# pickup3.net
KiCad netlist of a schematic drawn in EasyEDA
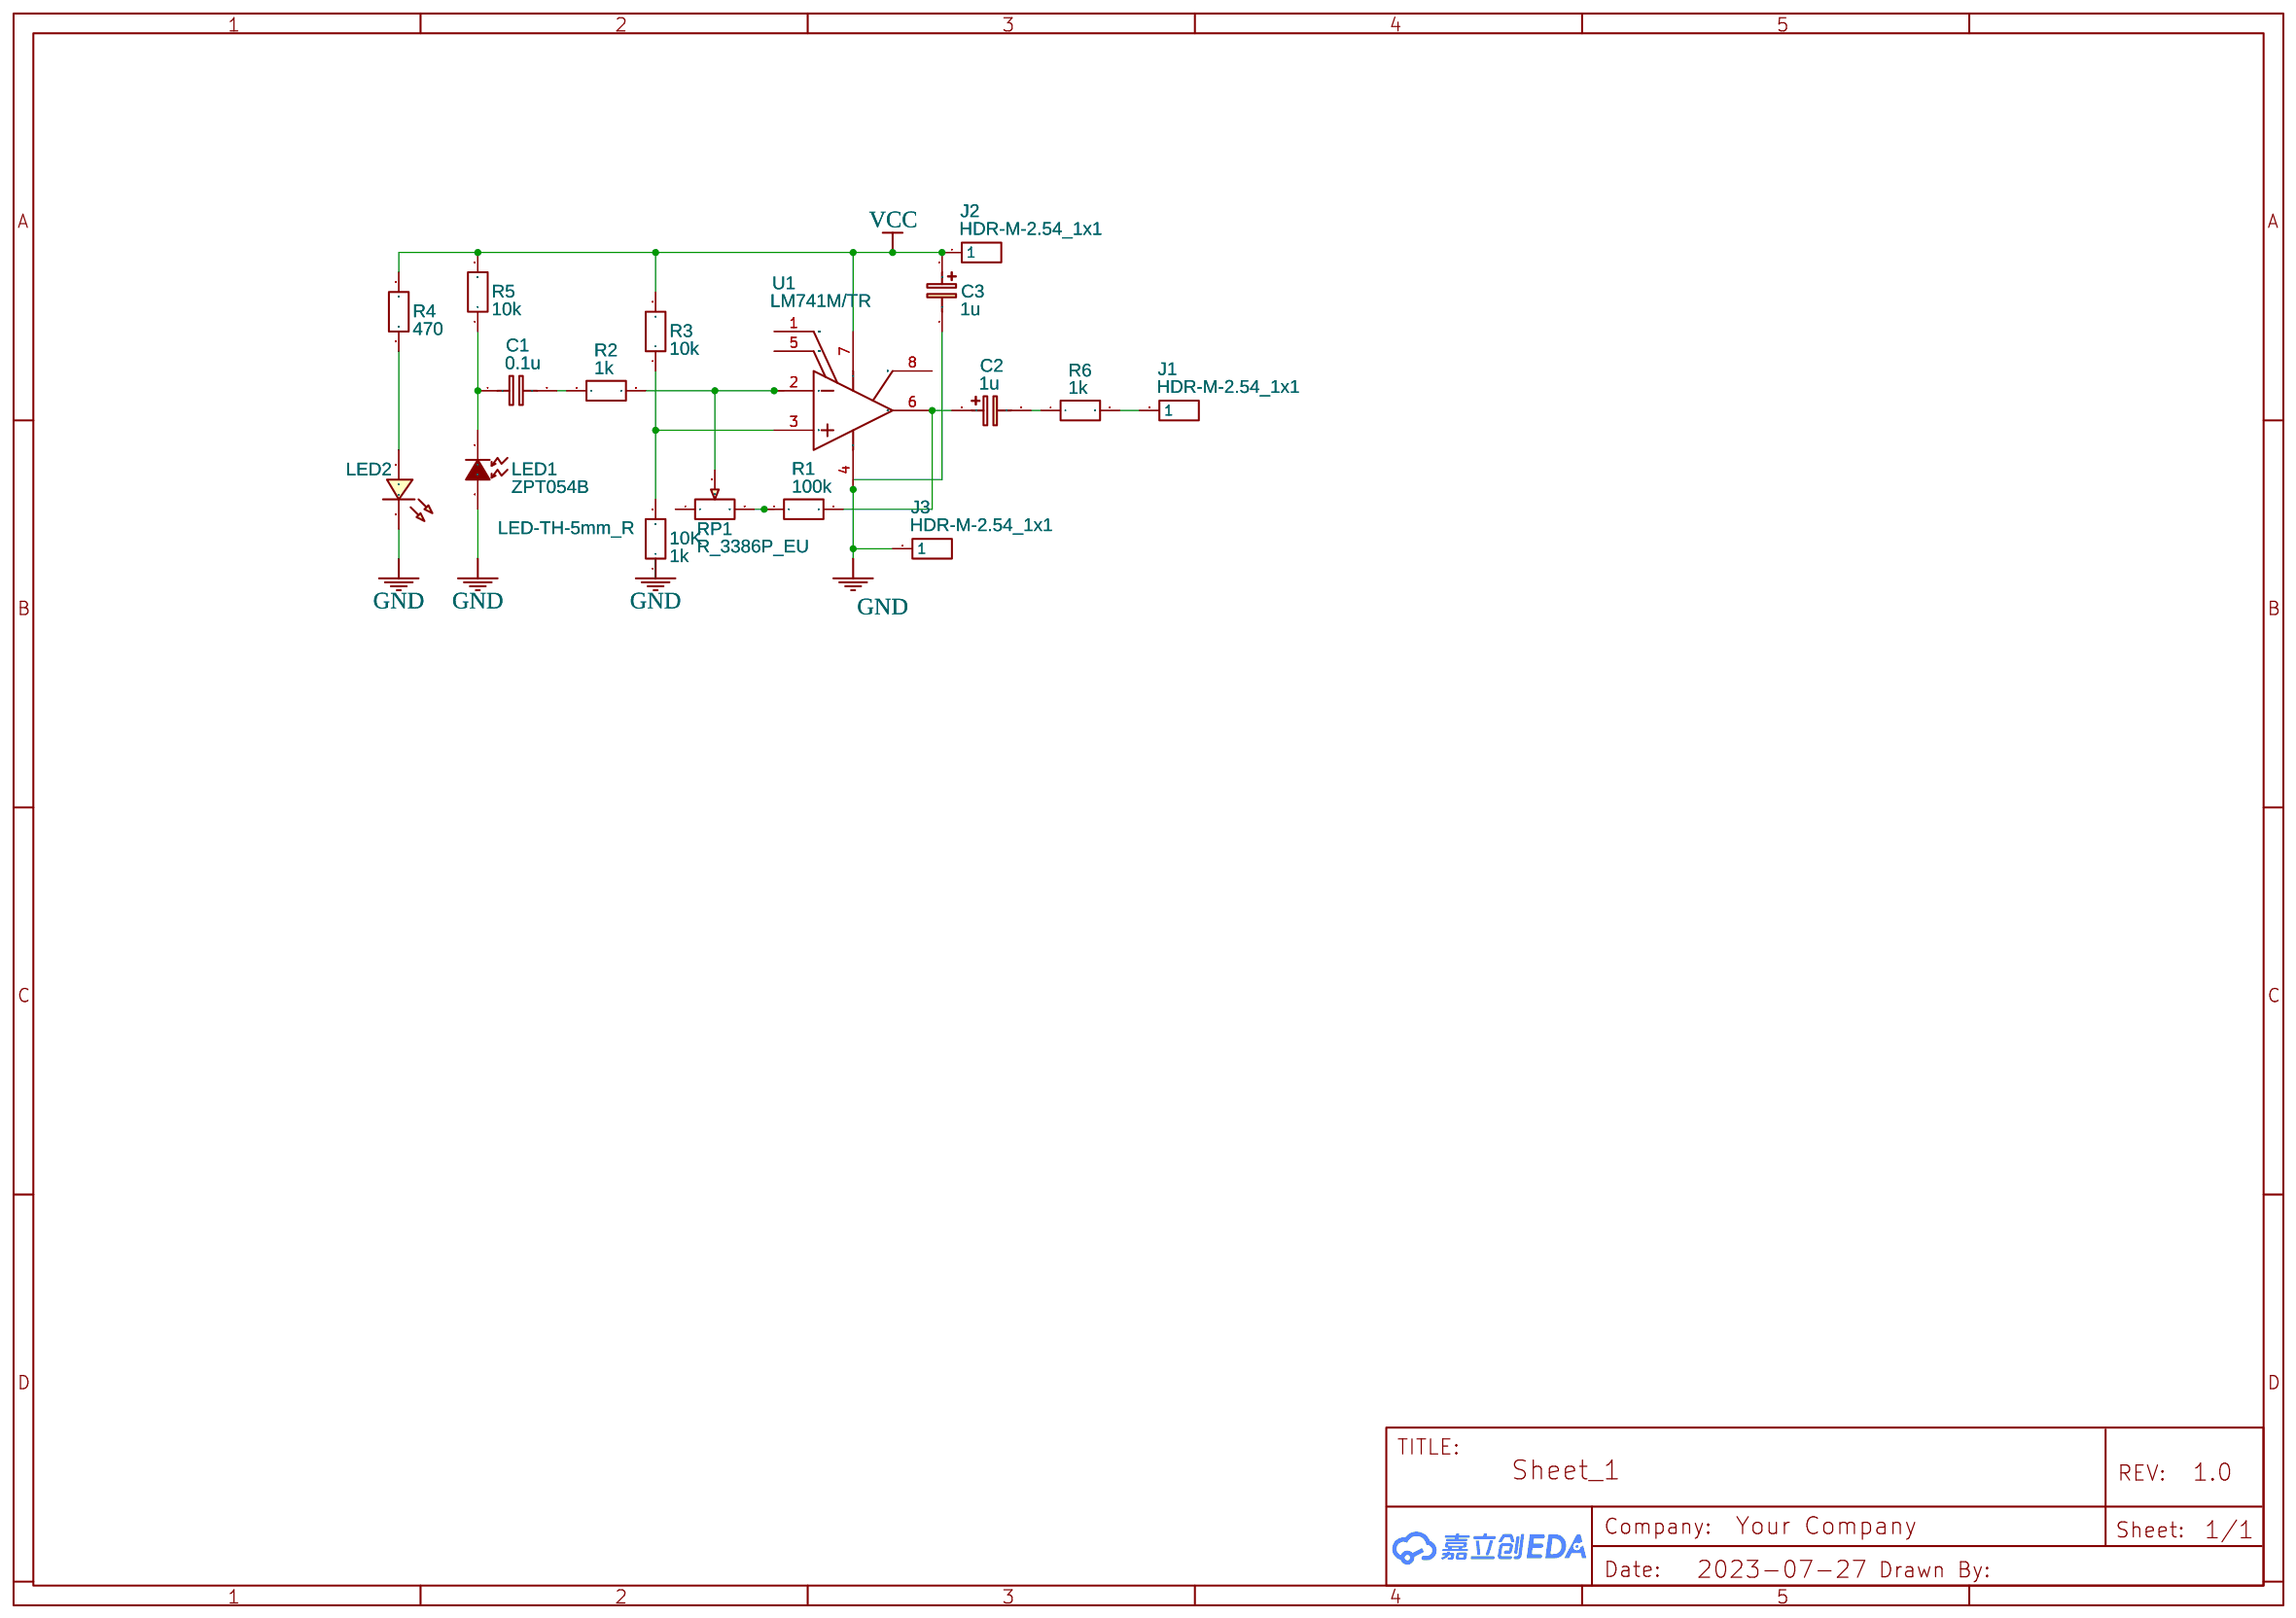
[diagram p0: schematic sheet]

(export (version "E")
  (design (tool "Eeschema 10.0.6"))
  (components
    (comp (ref "10K") (value "1k") (libsource (lib "") (part "R_0603_EU_2")))
    (comp (ref "C1") (value "0.1u") (libsource (lib "") (part "C_0603_EU")))
    (comp (ref "C2") (value "1u") (libsource (lib "") (part "C_Tan_SMD_A_EU_1")))
    (comp (ref "C3") (value "1u") (libsource (lib "") (part "C_Tan_SMD_A_EU")))
    (comp (ref "J1")
      (value "HDR-M-2.54_1x1")
      (fields (field (name "BOM_Supplier Part") "C81276"))
      (libsource (lib "") (part "HDR-M-2.54_1x1"))
    )
    (comp (ref "J2")
      (value "HDR-M-2.54_1x1")
      (fields (field (name "BOM_Supplier Part") "C81276"))
      (libsource (lib "") (part "HDR-M-2.54_1x1"))
    )
    (comp (ref "J3")
      (value "HDR-M-2.54_1x1")
      (fields (field (name "BOM_Supplier Part") "C81276"))
      (libsource (lib "") (part "HDR-M-2.54_1x1"))
    )
    (comp (ref "LED1")
      (value "ZPT054B")
      (fields (field (name "Manufacturer") "Chau Light"))
      (libsource (lib "") (part "ZPT054B"))
    )
    (comp (ref "LED2")
      (value "LED-TH-5mm_R")
      (fields
        (field (name "BOM_Manufacturer Part") "333-2SURD/S530-A3")
        (field (name "BOM_Supplier Part") "C87271")
      )
      (libsource (lib "") (part "LED-TH-5mm_R"))
    )
    (comp (ref "R1") (value "100k") (libsource (lib "") (part "R_0603_EU_1")))
    (comp (ref "R2") (value "1k") (libsource (lib "") (part "R_0603_EU_1")))
    (comp (ref "R3") (value "10k") (libsource (lib "") (part "R_0603_EU")))
    (comp (ref "R4") (value "470") (libsource (lib "") (part "R_0603_EU")))
    (comp (ref "R5") (value "10k") (libsource (lib "") (part "R_0603_EU")))
    (comp (ref "R6") (value "1k") (libsource (lib "") (part "R_0603_EU_1")))
    (comp (ref "RP1") (value "R_3386P_EU") (libsource (lib "") (part "R_3386P_EU")))
    (comp (ref "U1")
      (value "LM741M/TR")
      (fields (field (name "Manufacturer") "HGSEMI(华冠)"))
      (libsource (lib "") (part "LM741M/TR"))
    )
  )
  (nets
    (net (code "1") (name "GND") (class "Default")
      (node (ref "10K") (pin "1") (pinfunction "1_1") (pintype "unspecified"))
      (node (ref "C3") (pin "2") (pinfunction "2_2") (pintype "unspecified"))
      (node (ref "J3") (pin "1") (pinfunction "1_1") (pintype "input"))
      (node (ref "LED1") (pin "2") (pinfunction "C_2") (pintype "input"))
      (node (ref "LED2") (pin "2") (pinfunction "2_2") (pintype "unspecified"))
      (node (ref "U1") (pin "4") (pinfunction "V-_4") (pintype "passive"))
    )
    (net (code "2") (name "Net-(C1-Pad2)") (class "Default")
      (node (ref "C1") (pin "2") (pinfunction "2_2") (pintype "unspecified"))
      (node (ref "R2") (pin "1") (pinfunction "1_1") (pintype "unspecified"))
    )
    (net (code "3") (name "Net-(C2-Pad2)") (class "Default")
      (node (ref "C2") (pin "2") (pinfunction "2_2") (pintype "unspecified"))
      (node (ref "R6") (pin "1") (pinfunction "1_1") (pintype "unspecified"))
    )
    (net (code "4") (name "Net-(J1-Pad1)") (class "Default")
      (node (ref "J1") (pin "1") (pinfunction "1_1") (pintype "input"))
      (node (ref "R6") (pin "2") (pinfunction "2_2") (pintype "unspecified"))
    )
    (net (code "5") (name "Net-(LED1-E)") (class "Default")
      (node (ref "C1") (pin "1") (pinfunction "1_1") (pintype "unspecified"))
      (node (ref "LED1") (pin "1") (pinfunction "E_1") (pintype "input"))
      (node (ref "R5") (pin "1") (pinfunction "1_1") (pintype "unspecified"))
    )
    (net (code "6") (name "Net-(LED2-Pad1)") (class "Default")
      (node (ref "LED2") (pin "1") (pinfunction "1_1") (pintype "unspecified"))
      (node (ref "R4") (pin "1") (pinfunction "1_1") (pintype "unspecified"))
    )
    (net (code "7") (name "Net-(R1-Pad1)") (class "Default")
      (node (ref "R1") (pin "1") (pinfunction "1_1") (pintype "unspecified"))
      (node (ref "RP1") (pin "3") (pinfunction "3_3") (pintype "input"))
    )
    (net (code "8") (name "Net-(U1-IN+)") (class "Default")
      (node (ref "10K") (pin "2") (pinfunction "2_2") (pintype "unspecified"))
      (node (ref "R3") (pin "1") (pinfunction "1_1") (pintype "unspecified"))
      (node (ref "U1") (pin "3") (pinfunction "IN+_3") (pintype "unspecified"))
    )
    (net (code "9") (name "Net-(U1-IN-)") (class "Default")
      (node (ref "R2") (pin "2") (pinfunction "2_2") (pintype "unspecified"))
      (node (ref "RP1") (pin "2") (pinfunction "2_2") (pintype "input"))
      (node (ref "U1") (pin "2") (pinfunction "IN-_2") (pintype "unspecified"))
    )
    (net (code "10") (name "Net-(U1-OUT)") (class "Default")
      (node (ref "C2") (pin "1") (pinfunction "1_1") (pintype "unspecified"))
      (node (ref "R1") (pin "2") (pinfunction "2_2") (pintype "unspecified"))
      (node (ref "U1") (pin "6") (pinfunction "OUT_6") (pintype "output"))
    )
    (net (code "11") (name "VCC") (class "Default")
      (node (ref "C3") (pin "1") (pinfunction "1_1") (pintype "unspecified"))
      (node (ref "J2") (pin "1") (pinfunction "1_1") (pintype "input"))
      (node (ref "R3") (pin "2") (pinfunction "2_2") (pintype "unspecified"))
      (node (ref "R4") (pin "2") (pinfunction "2_2") (pintype "unspecified"))
      (node (ref "R5") (pin "2") (pinfunction "2_2") (pintype "unspecified"))
      (node (ref "U1") (pin "7") (pinfunction "V+_7") (pintype "passive"))
    )
    (net (code "12") (name "unconnected-(RP1-Pad1)") (class "Default")
      (node (ref "RP1") (pin "1") (pinfunction "1_1") (pintype "input"))
    )
    (net (code "13") (name "unconnected-(U1-NC-Pad8)") (class "Default")
      (node (ref "U1") (pin "8") (pinfunction "NC_8") (pintype "unspecified"))
    )
    (net (code "14") (name "unconnected-(U1-OFFSET_NULL-Pad1)") (class "Default")
      (node (ref "U1") (pin "1") (pinfunction "OFFSET_NULL_1") (pintype "unspecified"))
    )
    (net (code "15") (name "unconnected-(U1-OFFSET_NULL-Pad5)") (class "Default")
      (node (ref "U1") (pin "5") (pinfunction "OFFSET_NULL_5") (pintype "unspecified"))
    )
  )
)
